# erprog_1504-1.net
KiCad netlist of a schematic drawn in EAGLE
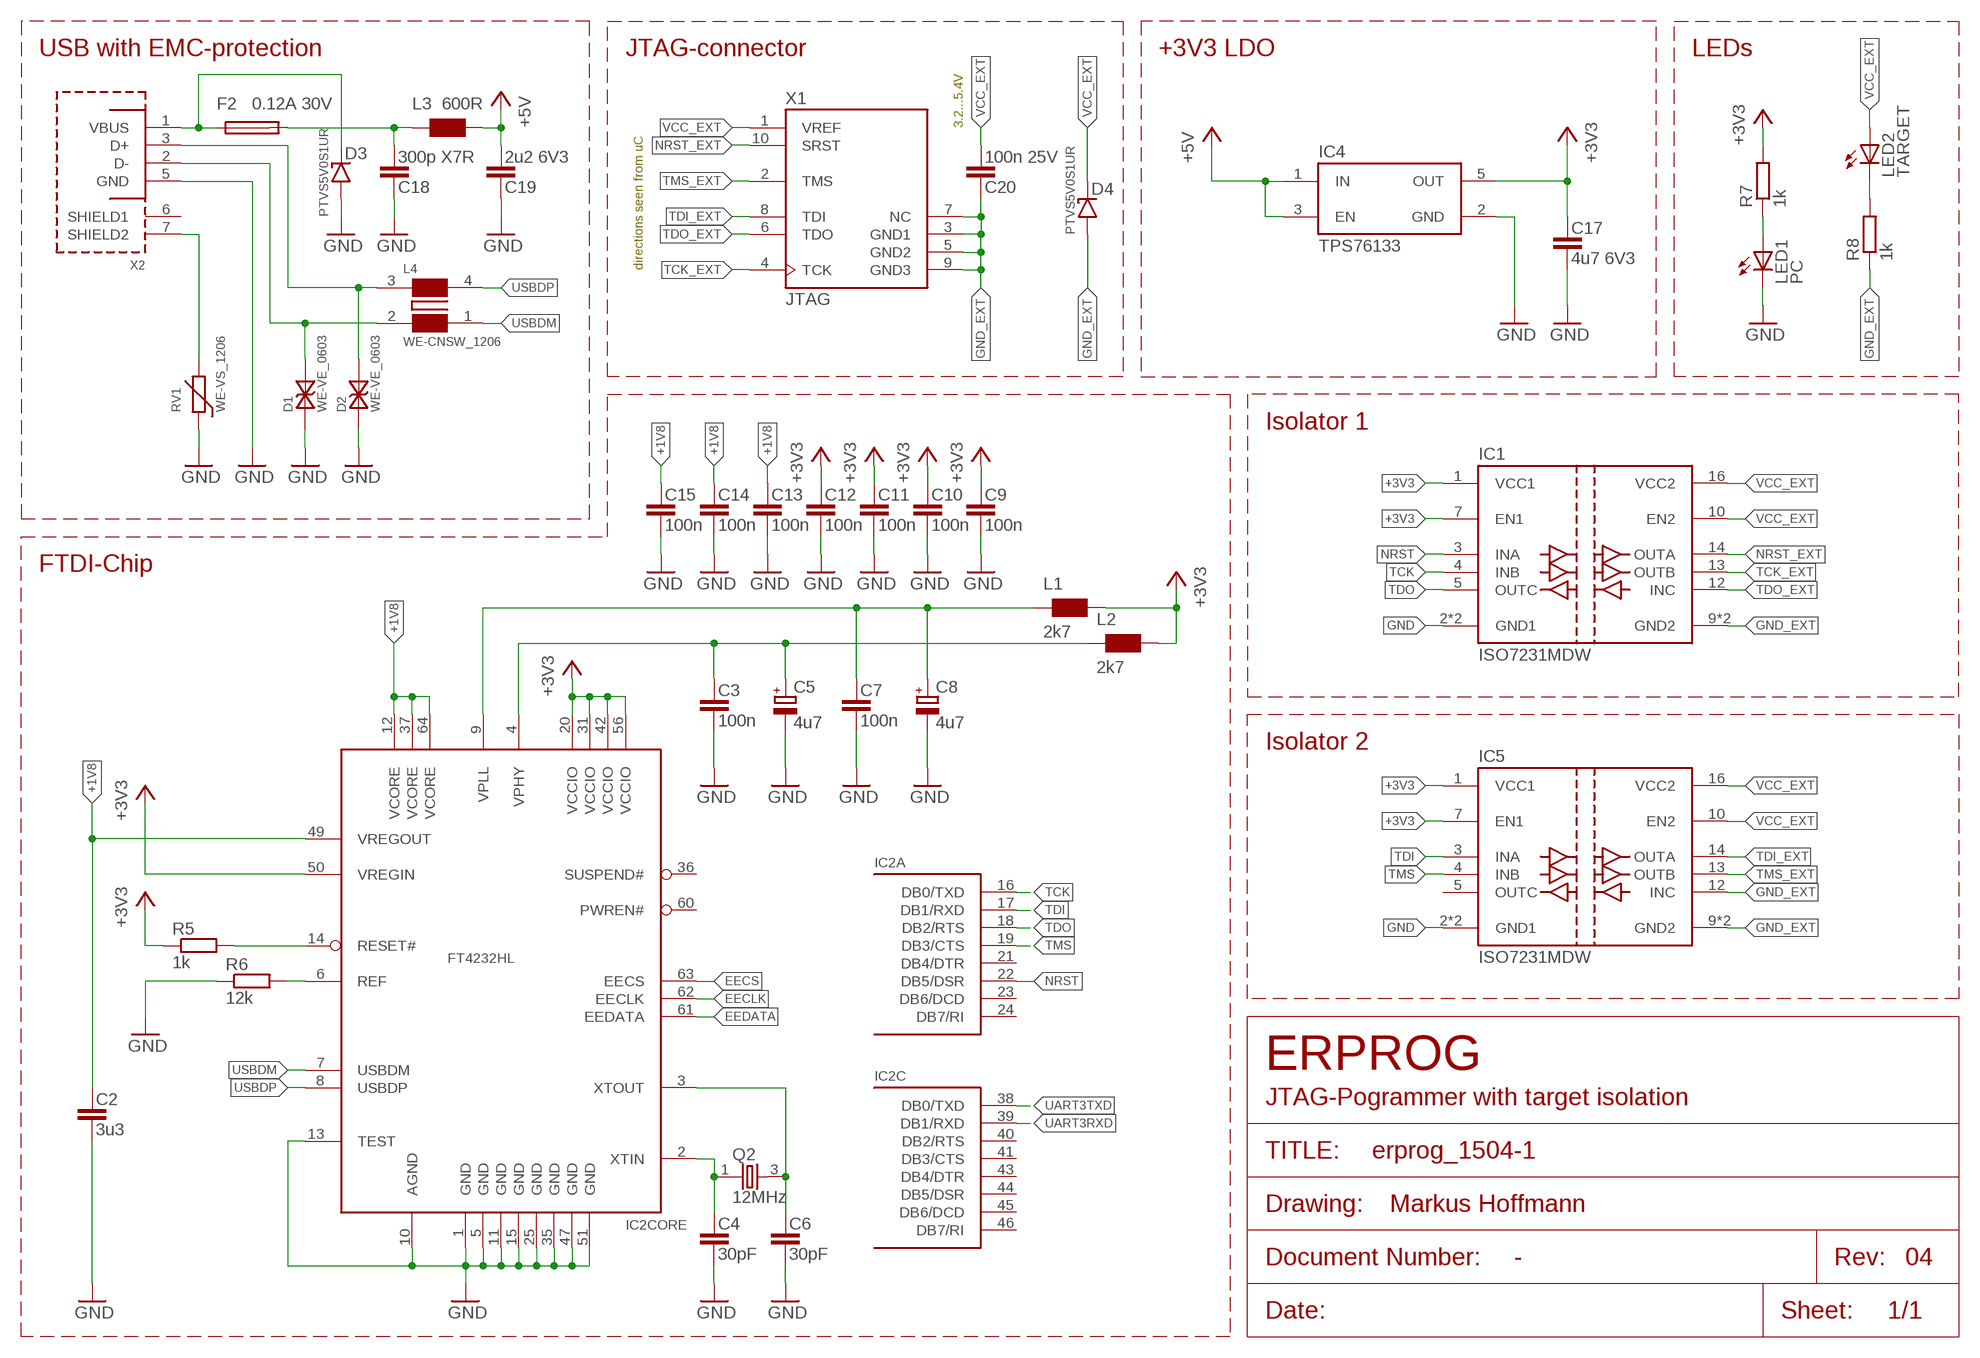
[diagram p0: schematic, sheet 1]

(export (version "E")
  (design (tool "Eeschema 10.0.6"))
  (components
    (comp (ref "C2")
      (value "3u3")
      (footprint "eagle-import:C0603")
      (libsource (lib "eagle-import") (part "C-EUC0603"))
    )
    (comp (ref "C3")
      (value "100n")
      (footprint "eagle-import:C0603")
      (libsource (lib "eagle-import") (part "C-EUC0603"))
    )
    (comp (ref "C4")
      (value "30pF")
      (footprint "eagle-import:C0603")
      (libsource (lib "eagle-import") (part "C-EUC0603"))
    )
    (comp (ref "C5")
      (value "4u7")
      (footprint "eagle-import:A_3216-18R")
      (libsource (lib "eagle-import") (part "CPOL-EUA/3216-18R"))
    )
    (comp (ref "C6")
      (value "30pF")
      (footprint "eagle-import:C0603")
      (libsource (lib "eagle-import") (part "C-EUC0603"))
    )
    (comp (ref "C7")
      (value "100n")
      (footprint "eagle-import:C0603")
      (libsource (lib "eagle-import") (part "C-EUC0603"))
    )
    (comp (ref "C8")
      (value "4u7")
      (footprint "eagle-import:A_3216-18R")
      (libsource (lib "eagle-import") (part "CPOL-EUA/3216-18R"))
    )
    (comp (ref "C9")
      (value "100n")
      (footprint "eagle-import:C0603")
      (libsource (lib "eagle-import") (part "C-EUC0603"))
    )
    (comp (ref "C10")
      (value "100n")
      (footprint "eagle-import:C0603")
      (libsource (lib "eagle-import") (part "C-EUC0603"))
    )
    (comp (ref "C11")
      (value "100n")
      (footprint "eagle-import:C0603")
      (libsource (lib "eagle-import") (part "C-EUC0603"))
    )
    (comp (ref "C12")
      (value "100n")
      (footprint "eagle-import:C0603")
      (libsource (lib "eagle-import") (part "C-EUC0603"))
    )
    (comp (ref "C13")
      (value "100n")
      (footprint "eagle-import:C0603")
      (libsource (lib "eagle-import") (part "C-EUC0603"))
    )
    (comp (ref "C14")
      (value "100n")
      (footprint "eagle-import:C0603")
      (libsource (lib "eagle-import") (part "C-EUC0603"))
    )
    (comp (ref "C15")
      (value "100n")
      (footprint "eagle-import:C0603")
      (libsource (lib "eagle-import") (part "C-EUC0603"))
    )
    (comp (ref "C17")
      (value "4u7 6V3")
      (footprint "eagle-import:C0805")
      (libsource (lib "eagle-import") (part "C-EUC0805"))
    )
    (comp (ref "C18")
      (value "300p X7R")
      (footprint "eagle-import:C0603")
      (libsource (lib "eagle-import") (part "C-EUC0603"))
    )
    (comp (ref "C19")
      (value "2u2 6V3")
      (footprint "eagle-import:C0603")
      (libsource (lib "eagle-import") (part "C-EUC0603"))
    )
    (comp (ref "C20")
      (value "100n 25V")
      (footprint "eagle-import:C0603")
      (libsource (lib "eagle-import") (part "C-EUC0603"))
    )
    (comp (ref "D1")
      (value "WE-VE_0603")
      (footprint "eagle-import:WESURGE_0603")
      (libsource (lib "eagle-import") (part "WE-VE_0603"))
    )
    (comp (ref "D2")
      (value "WE-VE_0603")
      (footprint "eagle-import:WESURGE_0603")
      (libsource (lib "eagle-import") (part "WE-VE_0603"))
    )
    (comp (ref "D3")
      (value "PTVS5V0S1UR")
      (footprint "eagle-import:SOD123")
      (libsource (lib "eagle-import") (part "PTVSS1UR5V0"))
    )
    (comp (ref "D4")
      (value "PTVS5V0S1UR")
      (footprint "eagle-import:SOD123")
      (libsource (lib "eagle-import") (part "PTVSS1UR5V0"))
    )
    (comp (ref "F2")
      (value "0.12A 30V")
      (footprint "eagle-import:MF-NSMF-1")
      (libsource (lib "eagle-import") (part "MF-NSMF012-2"))
    )
    (comp (ref "IC1")
      (value "ISO7231MDW")
      (footprint "eagle-import:SO16_SOT162-1")
      (libsource (lib "eagle-import") (part "ISO7231?DWM"))
    )
    (comp (ref "IC2")
      (value "FT4232HL")
      (footprint "eagle-import:LQFP64")
      (libsource (lib "eagle-import") (part "FT4232HL"))
    )
    (comp (ref "IC4")
      (value "TPS76133")
      (footprint "eagle-import:SOT-23-5")
      (libsource (lib "eagle-import") (part "TPS76SOT23133"))
    )
    (comp (ref "IC5")
      (value "ISO7231MDW")
      (footprint "eagle-import:SO16_SOT162-1")
      (libsource (lib "eagle-import") (part "ISO7231?DWM"))
    )
    (comp (ref "L1")
      (value "2k7")
      (footprint "eagle-import:0805")
      (libsource (lib "eagle-import") (part "WE-CBF_0805"))
    )
    (comp (ref "L2")
      (value "2k7")
      (footprint "eagle-import:0805")
      (libsource (lib "eagle-import") (part "WE-CBF_0805"))
    )
    (comp (ref "L3")
      (value "600R")
      (footprint "eagle-import:0805")
      (libsource (lib "eagle-import") (part "WE-CBF_0805"))
    )
    (comp (ref "L4")
      (value "WE-CNSW_1206")
      (footprint "eagle-import:WE-CNSW_1206")
      (libsource (lib "eagle-import") (part "WE-CNSW_1206"))
    )
    (comp (ref "LED1")
      (value "PC")
      (footprint "eagle-import:SML0805")
      (libsource (lib "eagle-import") (part "LEDSML0805"))
    )
    (comp (ref "LED2")
      (value "TARGET")
      (footprint "eagle-import:SML0805")
      (libsource (lib "eagle-import") (part "LEDSML0805"))
    )
    (comp (ref "Q2")
      (value "12MHz")
      (footprint "eagle-import:MQ")
      (libsource (lib "eagle-import") (part "MQ"))
    )
    (comp (ref "R5")
      (value "1k")
      (footprint "eagle-import:R0603")
      (libsource (lib "eagle-import") (part "R-EU_R0603"))
    )
    (comp (ref "R6")
      (value "12k")
      (footprint "eagle-import:R0603")
      (libsource (lib "eagle-import") (part "R-EU_R0603"))
    )
    (comp (ref "R7")
      (value "1k")
      (footprint "eagle-import:R0603")
      (libsource (lib "eagle-import") (part "R-EU_R0603"))
    )
    (comp (ref "R8")
      (value "1k")
      (footprint "eagle-import:R0603")
      (libsource (lib "eagle-import") (part "R-EU_R0603"))
    )
    (comp (ref "RV1")
      (value "WE-VS_1206")
      (footprint "eagle-import:WESURGE_1206")
      (libsource (lib "eagle-import") (part "WE-VS_1206"))
    )
    (comp (ref "X1")
      (value "JTAG")
      (footprint "eagle-import:ML10R")
      (libsource (lib "eagle-import") (part "CORESIGHT-JTAG-10THD10R"))
    )
    (comp (ref "X2")
      (value "USB-SHIELD-MINI-B-BUCHSE-R-ASSMANN")
      (footprint "eagle-import:USB-MINI-B-BUCHSE-R")
      (libsource (lib "eagle-import") (part "USB-SHIELD-MINI-B-BUCHSE-R-ASSMANN"))
    )
  )
  (nets
    (net (code "1") (name "+1V8") (class "Default")
      (node (ref "C13") (pin "1") (pinfunction "1_1") (pintype "passive"))
      (node (ref "C14") (pin "1") (pinfunction "1_1") (pintype "passive"))
      (node (ref "C15") (pin "1") (pinfunction "1_1") (pintype "passive"))
      (node (ref "C2") (pin "1") (pinfunction "1_1") (pintype "passive"))
      (node (ref "IC2") (pin "12") (pinfunction "VCORE_12") (pintype "power_in"))
      (node (ref "IC2") (pin "37") (pinfunction "VCORE_37") (pintype "power_in"))
      (node (ref "IC2") (pin "49") (pinfunction "VREGOUT_49") (pintype "output"))
      (node (ref "IC2") (pin "64") (pinfunction "VCORE_64") (pintype "power_in"))
    )
    (net (code "2") (name "+3V3") (class "Default")
      (node (ref "C10") (pin "1") (pinfunction "1_1") (pintype "passive"))
      (node (ref "C11") (pin "1") (pinfunction "1_1") (pintype "passive"))
      (node (ref "C12") (pin "1") (pinfunction "1_1") (pintype "passive"))
      (node (ref "C17") (pin "1") (pinfunction "1_1") (pintype "passive"))
      (node (ref "C9") (pin "1") (pinfunction "1_1") (pintype "passive"))
      (node (ref "IC1") (pin "1") (pinfunction "VCC1_1") (pintype "power_in"))
      (node (ref "IC1") (pin "7") (pinfunction "EN1_7") (pintype "input"))
      (node (ref "IC2") (pin "20") (pinfunction "VCCIO_20") (pintype "power_in"))
      (node (ref "IC2") (pin "31") (pinfunction "VCCIO_31") (pintype "power_in"))
      (node (ref "IC2") (pin "42") (pinfunction "VCCIO_42") (pintype "power_in"))
      (node (ref "IC2") (pin "50") (pinfunction "VREGIN_50") (pintype "bidirectional"))
      (node (ref "IC2") (pin "56") (pinfunction "VCCIO_56") (pintype "power_in"))
      (node (ref "IC4") (pin "5") (pinfunction "OUT_5") (pintype "bidirectional"))
      (node (ref "IC5") (pin "1") (pinfunction "VCC1_1") (pintype "power_in"))
      (node (ref "IC5") (pin "7") (pinfunction "EN1_7") (pintype "input"))
      (node (ref "L1") (pin "2") (pinfunction "2_2") (pintype "passive"))
      (node (ref "L2") (pin "2") (pinfunction "2_2") (pintype "passive"))
      (node (ref "R5") (pin "1") (pinfunction "1_1") (pintype "passive"))
      (node (ref "R7") (pin "2") (pinfunction "2_2") (pintype "passive"))
    )
    (net (code "3") (name "+5V") (class "Default")
      (node (ref "C19") (pin "2") (pinfunction "2_2") (pintype "passive"))
      (node (ref "IC4") (pin "1") (pinfunction "IN_1") (pintype "bidirectional"))
      (node (ref "IC4") (pin "3") (pinfunction "EN_3") (pintype "bidirectional"))
      (node (ref "L3") (pin "2") (pinfunction "2_2") (pintype "passive"))
    )
    (net (code "4") (name "EECLK") (class "Default")
      (node (ref "IC2") (pin "62") (pinfunction "EECLK_62") (pintype "output"))
    )
    (net (code "5") (name "EECS") (class "Default")
      (node (ref "IC2") (pin "63") (pinfunction "EECS_63") (pintype "bidirectional"))
    )
    (net (code "6") (name "EEDATA") (class "Default")
      (node (ref "IC2") (pin "61") (pinfunction "EEDATA_61") (pintype "bidirectional"))
    )
    (net (code "7") (name "GND") (class "Default")
      (node (ref "C10") (pin "2") (pinfunction "2_2") (pintype "passive"))
      (node (ref "C11") (pin "2") (pinfunction "2_2") (pintype "passive"))
      (node (ref "C12") (pin "2") (pinfunction "2_2") (pintype "passive"))
      (node (ref "C13") (pin "2") (pinfunction "2_2") (pintype "passive"))
      (node (ref "C14") (pin "2") (pinfunction "2_2") (pintype "passive"))
      (node (ref "C15") (pin "2") (pinfunction "2_2") (pintype "passive"))
      (node (ref "C17") (pin "2") (pinfunction "2_2") (pintype "passive"))
      (node (ref "C18") (pin "1") (pinfunction "1_1") (pintype "passive"))
      (node (ref "C19") (pin "1") (pinfunction "1_1") (pintype "passive"))
      (node (ref "C2") (pin "2") (pinfunction "2_2") (pintype "passive"))
      (node (ref "C3") (pin "2") (pinfunction "2_2") (pintype "passive"))
      (node (ref "C4") (pin "2") (pinfunction "2_2") (pintype "passive"))
      (node (ref "C5") (pin "-") (pinfunction "-_-") (pintype "passive"))
      (node (ref "C6") (pin "2") (pinfunction "2_2") (pintype "passive"))
      (node (ref "C7") (pin "2") (pinfunction "2_2") (pintype "passive"))
      (node (ref "C8") (pin "-") (pinfunction "-_-") (pintype "passive"))
      (node (ref "C9") (pin "2") (pinfunction "2_2") (pintype "passive"))
      (node (ref "D1") (pin "2") (pinfunction "2_2") (pintype "passive"))
      (node (ref "D2") (pin "2") (pinfunction "2_2") (pintype "passive"))
      (node (ref "D3") (pin "A") (pinfunction "ANODE_A") (pintype "bidirectional"))
      (node (ref "IC1") (pin "2") (pinfunction "GND1_2") (pintype "power_in"))
      (node (ref "IC1") (pin "8") (pinfunction "GND1_8") (pintype "power_in"))
      (node (ref "IC2") (pin "1") (pinfunction "GND_1") (pintype "power_in"))
      (node (ref "IC2") (pin "10") (pinfunction "AGND_10") (pintype "power_in"))
      (node (ref "IC2") (pin "11") (pinfunction "GND_11") (pintype "power_in"))
      (node (ref "IC2") (pin "13") (pinfunction "TEST_13") (pintype "input"))
      (node (ref "IC2") (pin "15") (pinfunction "GND_15") (pintype "power_in"))
      (node (ref "IC2") (pin "25") (pinfunction "GND_25") (pintype "power_in"))
      (node (ref "IC2") (pin "35") (pinfunction "GND_35") (pintype "power_in"))
      (node (ref "IC2") (pin "47") (pinfunction "GND_47") (pintype "power_in"))
      (node (ref "IC2") (pin "5") (pinfunction "GND_5") (pintype "power_in"))
      (node (ref "IC2") (pin "51") (pinfunction "GND_51") (pintype "power_in"))
      (node (ref "IC4") (pin "2") (pinfunction "GND_2") (pintype "bidirectional"))
      (node (ref "IC5") (pin "2") (pinfunction "GND1_2") (pintype "power_in"))
      (node (ref "IC5") (pin "8") (pinfunction "GND1_8") (pintype "power_in"))
      (node (ref "LED1") (pin "C") (pinfunction "C_C") (pintype "passive"))
      (node (ref "R6") (pin "1") (pinfunction "1_1") (pintype "passive"))
      (node (ref "RV1") (pin "1") (pinfunction "1_1") (pintype "passive"))
      (node (ref "X2") (pin "5") (pinfunction "GND_5") (pintype "bidirectional"))
    )
    (net (code "8") (name "GND_EXT") (class "Default")
      (node (ref "C20") (pin "1") (pinfunction "1_1") (pintype "passive"))
      (node (ref "D4") (pin "A") (pinfunction "ANODE_A") (pintype "bidirectional"))
      (node (ref "IC1") (pin "15") (pinfunction "GND2_15") (pintype "power_in"))
      (node (ref "IC1") (pin "9") (pinfunction "GND2_9") (pintype "power_in"))
      (node (ref "IC5") (pin "12") (pinfunction "INC_12") (pintype "input"))
      (node (ref "IC5") (pin "15") (pinfunction "GND2_15") (pintype "power_in"))
      (node (ref "IC5") (pin "9") (pinfunction "GND2_9") (pintype "power_in"))
      (node (ref "R8") (pin "1") (pinfunction "1_1") (pintype "passive"))
      (node (ref "X1") (pin "3") (pinfunction "GND1_3") (pintype "power_in"))
      (node (ref "X1") (pin "5") (pinfunction "GND2_5") (pintype "power_in"))
      (node (ref "X1") (pin "7") (pinfunction "NC_7") (pintype "bidirectional"))
      (node (ref "X1") (pin "9") (pinfunction "GND3_9") (pintype "power_in"))
    )
    (net (code "9") (name "NRST") (class "Default")
      (node (ref "IC1") (pin "3") (pinfunction "INA_3") (pintype "input"))
      (node (ref "IC2") (pin "22") (pinfunction "DB5/DSR_22") (pintype "bidirectional"))
    )
    (net (code "10") (name "NRST_EXT") (class "Default")
      (node (ref "IC1") (pin "14") (pinfunction "OUTA_14") (pintype "output"))
      (node (ref "X1") (pin "10") (pinfunction "SRST_10") (pintype "bidirectional"))
    )
    (net (code "11") (name "Net-(C18-Pad2)") (class "Default")
      (node (ref "C18") (pin "2") (pinfunction "2_2") (pintype "passive"))
      (node (ref "F2") (pin "2") (pinfunction "2_2") (pintype "passive"))
      (node (ref "L3") (pin "1") (pinfunction "1_1") (pintype "passive"))
    )
    (net (code "12") (name "Net-(D3-KATHODE)") (class "Default")
      (node (ref "D3") (pin "C") (pinfunction "KATHODE_C") (pintype "bidirectional"))
      (node (ref "F2") (pin "1") (pinfunction "1_1") (pintype "passive"))
      (node (ref "X2") (pin "1") (pinfunction "VBUS_1") (pintype "bidirectional"))
    )
    (net (code "13") (name "Net-(IC2D-REF)") (class "Default")
      (node (ref "IC2") (pin "6") (pinfunction "REF_6") (pintype "input"))
      (node (ref "R6") (pin "2") (pinfunction "2_2") (pintype "passive"))
    )
    (net (code "14") (name "Net-(IC2D-RESET#)") (class "Default")
      (node (ref "IC2") (pin "14") (pinfunction "RESET#_14") (pintype "input"))
      (node (ref "R5") (pin "2") (pinfunction "2_2") (pintype "passive"))
    )
    (net (code "15") (name "Net-(IC2D-VPHY)") (class "Default")
      (node (ref "C3") (pin "1") (pinfunction "1_1") (pintype "passive"))
      (node (ref "C5") (pin "+") (pinfunction "+_+") (pintype "passive"))
      (node (ref "IC2") (pin "4") (pinfunction "VPHY_4") (pintype "power_in"))
      (node (ref "L2") (pin "1") (pinfunction "1_1") (pintype "passive"))
    )
    (net (code "16") (name "Net-(IC2D-VPLL)") (class "Default")
      (node (ref "C7") (pin "1") (pinfunction "1_1") (pintype "passive"))
      (node (ref "C8") (pin "+") (pinfunction "+_+") (pintype "passive"))
      (node (ref "IC2") (pin "9") (pinfunction "VPLL_9") (pintype "power_in"))
      (node (ref "L1") (pin "1") (pinfunction "1_1") (pintype "passive"))
    )
    (net (code "17") (name "Net-(IC2D-XTIN)") (class "Default")
      (node (ref "C4") (pin "1") (pinfunction "1_1") (pintype "passive"))
      (node (ref "IC2") (pin "2") (pinfunction "XTIN_2") (pintype "input"))
      (node (ref "Q2") (pin "1") (pinfunction "1_1") (pintype "passive"))
    )
    (net (code "18") (name "Net-(IC2D-XTOUT)") (class "Default")
      (node (ref "C6") (pin "1") (pinfunction "1_1") (pintype "passive"))
      (node (ref "IC2") (pin "3") (pinfunction "XTOUT_3") (pintype "output"))
      (node (ref "Q2") (pin "3") (pinfunction "2_3") (pintype "passive"))
    )
    (net (code "19") (name "Net-(L4-4)") (class "Default")
      (node (ref "D2") (pin "1") (pinfunction "1_1") (pintype "passive"))
      (node (ref "L4") (pin "3") (pinfunction "4_3") (pintype "passive"))
      (node (ref "X2") (pin "3") (pinfunction "D+_3") (pintype "bidirectional"))
    )
    (net (code "20") (name "Net-(LED1-PadA)") (class "Default")
      (node (ref "LED1") (pin "A") (pinfunction "A_A") (pintype "passive"))
      (node (ref "R7") (pin "1") (pinfunction "1_1") (pintype "passive"))
    )
    (net (code "21") (name "Net-(LED2-PadC)") (class "Default")
      (node (ref "LED2") (pin "C") (pinfunction "C_C") (pintype "passive"))
      (node (ref "R8") (pin "2") (pinfunction "2_2") (pintype "passive"))
    )
    (net (code "22") (name "Net-(X2-D-)") (class "Default")
      (node (ref "D1") (pin "1") (pinfunction "1_1") (pintype "passive"))
      (node (ref "L4") (pin "2") (pinfunction "2_2") (pintype "passive"))
      (node (ref "X2") (pin "2") (pinfunction "D-_2") (pintype "bidirectional"))
    )
    (net (code "23") (name "Net-(X2-SHIELD2)") (class "Default")
      (node (ref "RV1") (pin "2") (pinfunction "2_2") (pintype "passive"))
      (node (ref "X2") (pin "7") (pinfunction "SHIELD2_7") (pintype "bidirectional"))
    )
    (net (code "24") (name "TCK") (class "Default")
      (node (ref "IC1") (pin "4") (pinfunction "INB_4") (pintype "input"))
      (node (ref "IC2") (pin "16") (pinfunction "DB0/TXD_16") (pintype "bidirectional"))
    )
    (net (code "25") (name "TCK_EXT") (class "Default")
      (node (ref "IC1") (pin "13") (pinfunction "OUTB_13") (pintype "output"))
      (node (ref "X1") (pin "4") (pinfunction "TCK_4") (pintype "bidirectional"))
    )
    (net (code "26") (name "TDI") (class "Default")
      (node (ref "IC2") (pin "17") (pinfunction "DB1/RXD_17") (pintype "bidirectional"))
      (node (ref "IC5") (pin "3") (pinfunction "INA_3") (pintype "input"))
    )
    (net (code "27") (name "TDI_EXT") (class "Default")
      (node (ref "IC5") (pin "14") (pinfunction "OUTA_14") (pintype "output"))
      (node (ref "X1") (pin "8") (pinfunction "TDI_8") (pintype "bidirectional"))
    )
    (net (code "28") (name "TDO") (class "Default")
      (node (ref "IC1") (pin "5") (pinfunction "OUTC_5") (pintype "output"))
      (node (ref "IC2") (pin "18") (pinfunction "DB2/RTS_18") (pintype "bidirectional"))
    )
    (net (code "29") (name "TDO_EXT") (class "Default")
      (node (ref "IC1") (pin "12") (pinfunction "INC_12") (pintype "input"))
      (node (ref "X1") (pin "6") (pinfunction "TDO_6") (pintype "bidirectional"))
    )
    (net (code "30") (name "TMS") (class "Default")
      (node (ref "IC2") (pin "19") (pinfunction "DB3/CTS_19") (pintype "bidirectional"))
      (node (ref "IC5") (pin "4") (pinfunction "INB_4") (pintype "input"))
    )
    (net (code "31") (name "TMS_EXT") (class "Default")
      (node (ref "IC5") (pin "13") (pinfunction "OUTB_13") (pintype "output"))
      (node (ref "X1") (pin "2") (pinfunction "TMS_2") (pintype "bidirectional"))
    )
    (net (code "32") (name "UART3RXD") (class "Default")
      (node (ref "IC2") (pin "39") (pinfunction "DB1/RXD_39") (pintype "bidirectional"))
    )
    (net (code "33") (name "UART3TXD") (class "Default")
      (node (ref "IC2") (pin "38") (pinfunction "DB0/TXD_38") (pintype "bidirectional"))
    )
    (net (code "34") (name "USBDM") (class "Default")
      (node (ref "IC2") (pin "7") (pinfunction "USBDM_7") (pintype "input"))
      (node (ref "L4") (pin "1") (pinfunction "1_1") (pintype "passive"))
    )
    (net (code "35") (name "USBDP") (class "Default")
      (node (ref "IC2") (pin "8") (pinfunction "USBDP_8") (pintype "input"))
      (node (ref "L4") (pin "4") (pinfunction "3_4") (pintype "passive"))
    )
    (net (code "36") (name "VCC_EXT") (class "Default")
      (node (ref "C20") (pin "2") (pinfunction "2_2") (pintype "passive"))
      (node (ref "D4") (pin "C") (pinfunction "KATHODE_C") (pintype "bidirectional"))
      (node (ref "IC1") (pin "10") (pinfunction "EN2_10") (pintype "input"))
      (node (ref "IC1") (pin "16") (pinfunction "VCC2_16") (pintype "power_in"))
      (node (ref "IC5") (pin "10") (pinfunction "EN2_10") (pintype "input"))
      (node (ref "IC5") (pin "16") (pinfunction "VCC2_16") (pintype "power_in"))
      (node (ref "LED2") (pin "A") (pinfunction "A_A") (pintype "passive"))
      (node (ref "X1") (pin "1") (pinfunction "VREF_1") (pintype "power_in"))
    )
    (net (code "37") (name "unconnected-(IC2A-DB4{slash}DTR-Pad21)") (class "Default")
      (node (ref "IC2") (pin "21") (pinfunction "DB4/DTR_21") (pintype "bidirectional"))
    )
    (net (code "38") (name "unconnected-(IC2A-DB6{slash}DCD-Pad23)") (class "Default")
      (node (ref "IC2") (pin "23") (pinfunction "DB6/DCD_23") (pintype "bidirectional"))
    )
    (net (code "39") (name "unconnected-(IC2A-DB7{slash}RI-Pad24)") (class "Default")
      (node (ref "IC2") (pin "24") (pinfunction "DB7/RI_24") (pintype "bidirectional"))
    )
    (net (code "40") (name "unconnected-(IC2C-DB2{slash}RTS-Pad40)") (class "Default")
      (node (ref "IC2") (pin "40") (pinfunction "DB2/RTS_40") (pintype "bidirectional"))
    )
    (net (code "41") (name "unconnected-(IC2C-DB3{slash}CTS-Pad41)") (class "Default")
      (node (ref "IC2") (pin "41") (pinfunction "DB3/CTS_41") (pintype "bidirectional"))
    )
    (net (code "42") (name "unconnected-(IC2C-DB4{slash}DTR-Pad43)") (class "Default")
      (node (ref "IC2") (pin "43") (pinfunction "DB4/DTR_43") (pintype "bidirectional"))
    )
    (net (code "43") (name "unconnected-(IC2C-DB5{slash}DSR-Pad44)") (class "Default")
      (node (ref "IC2") (pin "44") (pinfunction "DB5/DSR_44") (pintype "bidirectional"))
    )
    (net (code "44") (name "unconnected-(IC2C-DB6{slash}DCD-Pad45)") (class "Default")
      (node (ref "IC2") (pin "45") (pinfunction "DB6/DCD_45") (pintype "bidirectional"))
    )
    (net (code "45") (name "unconnected-(IC2C-DB7{slash}RI-Pad46)") (class "Default")
      (node (ref "IC2") (pin "46") (pinfunction "DB7/RI_46") (pintype "bidirectional"))
    )
    (net (code "46") (name "unconnected-(IC2D-PWREN#-Pad60)") (class "Default")
      (node (ref "IC2") (pin "60") (pinfunction "PWREN#_60") (pintype "output"))
    )
    (net (code "47") (name "unconnected-(IC2D-SUSPEND#-Pad36)") (class "Default")
      (node (ref "IC2") (pin "36") (pinfunction "SUSPEND#_36") (pintype "output"))
    )
    (net (code "48") (name "unconnected-(IC5-OUTC-Pad5)") (class "Default")
      (node (ref "IC5") (pin "5") (pinfunction "OUTC_5") (pintype "output"))
    )
    (net (code "49") (name "unconnected-(X2-SHIELD1-Pad6)") (class "Default")
      (node (ref "X2") (pin "6") (pinfunction "SHIELD1_6") (pintype "bidirectional"))
    )
  )
)
